# bilancia_smart_pezzi_ali_cc.net
KiCad netlist of a schematic drawn in EAGLE
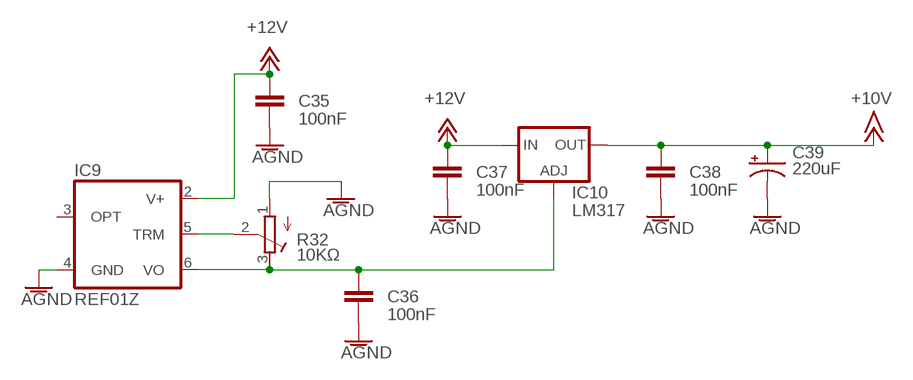
[diagram p0: schematic, sheet 1]

(export (version "E")
  (design (tool "Eeschema 10.0.6"))
  (components
    (comp (ref "C35")
      (value "100nF")
      (footprint "eagle-import:C2.5-2")
      (libsource (lib "eagle-import") (part "C2.5/2"))
    )
    (comp (ref "C36")
      (value "100nF")
      (footprint "eagle-import:C2.5-2")
      (libsource (lib "eagle-import") (part "C2.5/2"))
    )
    (comp (ref "C37")
      (value "100nF")
      (footprint "eagle-import:C2.5-2")
      (libsource (lib "eagle-import") (part "C2.5/2"))
    )
    (comp (ref "C38")
      (value "100nF")
      (footprint "eagle-import:C2.5-2")
      (libsource (lib "eagle-import") (part "C2.5/2"))
    )
    (comp (ref "C39")
      (value "220uF")
      (footprint "eagle-import:CPOL-RADIAL-100UF-25V")
      (libsource (lib "eagle-import") (part "CAP_POLPTH1"))
    )
    (comp (ref "IC9")
      (value "REF01Z")
      (footprint "eagle-import:DIL08")
      (libsource (lib "eagle-import") (part "REF01Z"))
    )
    (comp (ref "IC10")
      (value "LM317")
      (footprint "eagle-import:317TS")
      (libsource (lib "eagle-import") (part "LM317TS"))
    )
    (comp (ref "R32")
      (value "10KΩ")
      (footprint "eagle-import:RTRIM64W")
      (libsource (lib "eagle-import") (part "R-TRIMM64W"))
    )
  )
  (nets
    (net (code "1") (name "+10V") (class "Default")
      (node (ref "C38") (pin "2") (pinfunction "2_2") (pintype "passive"))
      (node (ref "C39") (pin "1") (pinfunction "+_1") (pintype "passive"))
      (node (ref "IC10") (pin "2") (pinfunction "OUT_2") (pintype "passive"))
    )
    (net (code "2") (name "+12V") (class "Default")
      (node (ref "C35") (pin "2") (pinfunction "2_2") (pintype "passive"))
      (node (ref "C37") (pin "2") (pinfunction "2_2") (pintype "passive"))
      (node (ref "IC10") (pin "3") (pinfunction "IN_3") (pintype "input"))
      (node (ref "IC9") (pin "2") (pinfunction "V+_2") (pintype "power_in"))
    )
    (net (code "3") (name "AGND") (class "Default")
      (node (ref "C35") (pin "1") (pinfunction "1_1") (pintype "passive"))
      (node (ref "C36") (pin "1") (pinfunction "1_1") (pintype "passive"))
      (node (ref "C37") (pin "1") (pinfunction "1_1") (pintype "passive"))
      (node (ref "C38") (pin "1") (pinfunction "1_1") (pintype "passive"))
      (node (ref "C39") (pin "2") (pinfunction "-_2") (pintype "passive"))
      (node (ref "IC9") (pin "4") (pinfunction "GND_4") (pintype "power_in"))
      (node (ref "R32") (pin "1") (pinfunction "E_1") (pintype "passive"))
    )
    (net (code "4") (name "Net-(IC9-TRM)") (class "Default")
      (node (ref "IC9") (pin "5") (pinfunction "TRM_5") (pintype "input"))
      (node (ref "R32") (pin "2") (pinfunction "S_2") (pintype "passive"))
    )
    (net (code "5") (name "Net-(IC10-ADJ)") (class "Default")
      (node (ref "C36") (pin "2") (pinfunction "2_2") (pintype "passive"))
      (node (ref "IC10") (pin "1") (pinfunction "ADJ_1") (pintype "input"))
      (node (ref "IC9") (pin "6") (pinfunction "VO_6") (pintype "output"))
      (node (ref "R32") (pin "3") (pinfunction "A_3") (pintype "passive"))
    )
    (net (code "6") (name "unconnected-(IC9-OPT-Pad3)") (class "Default")
      (node (ref "IC9") (pin "3") (pinfunction "OPT_3") (pintype "output"))
    )
  )
)
